# PB_ExtenderPlug.net
KiCad netlist of a schematic drawn in Altium Designer
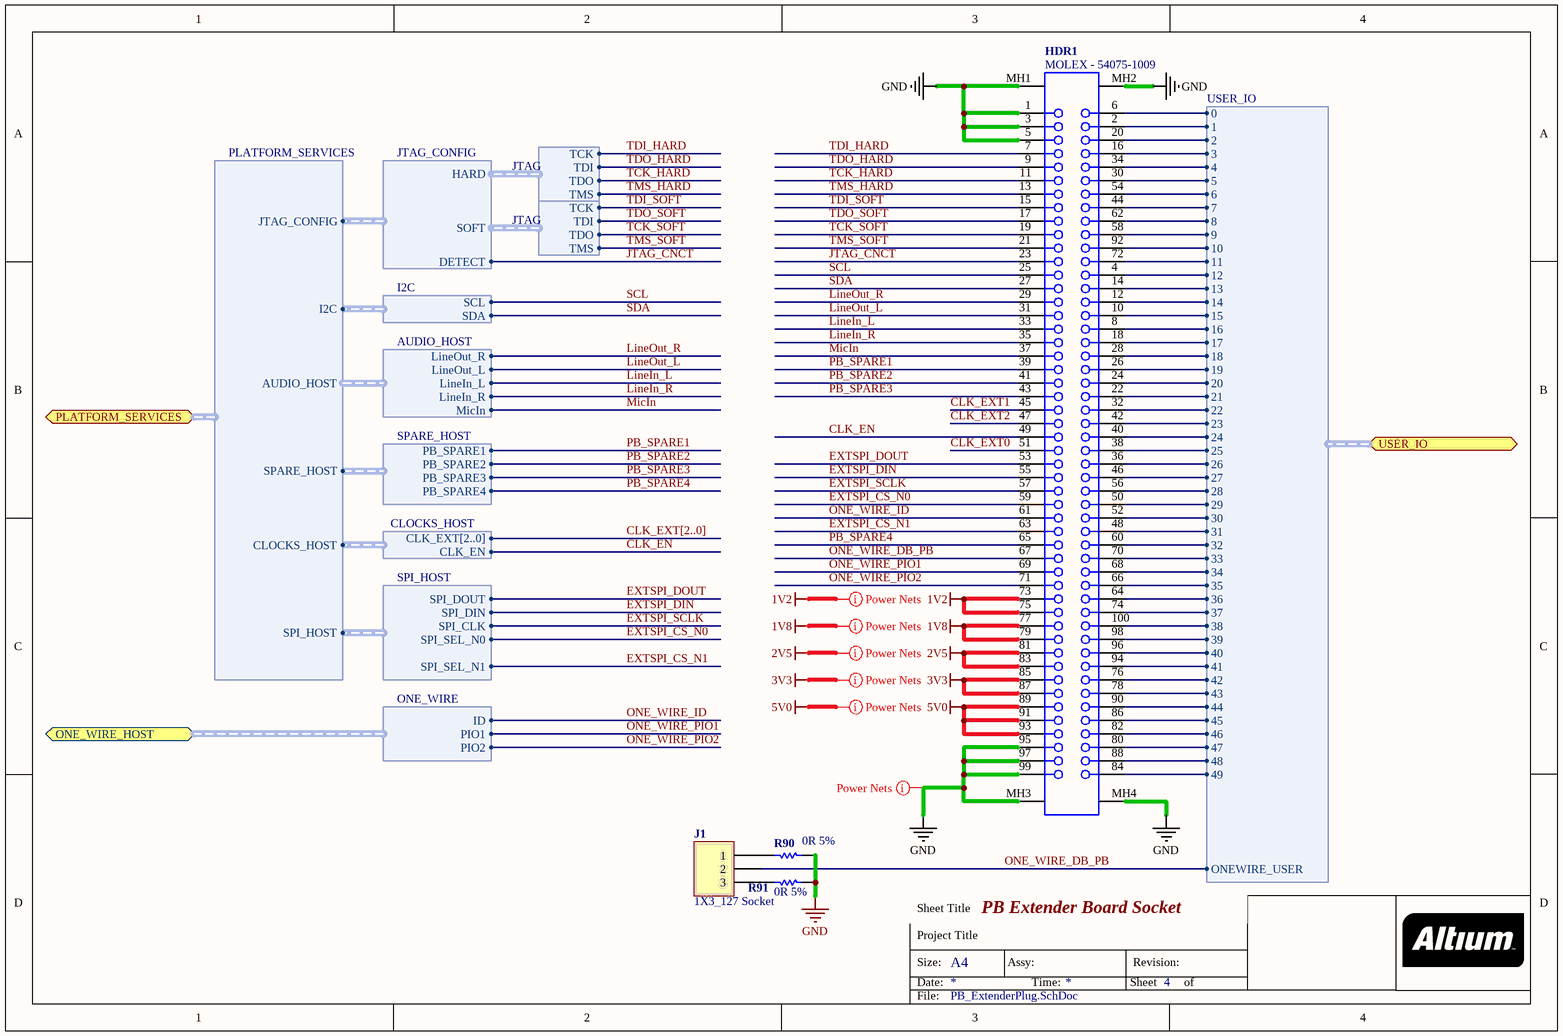
[diagram p0: PB_ExtenderPlug.SchDoc]

(export (version "E")
  (design (tool "Eeschema 10.0.6"))
  (components
    (comp (ref "HDR1")
      (value "MOLEX - 54075-1009")
      (footprint "54075")
      (description "Connector, Molex Docking Station 100 Pin Male 54075")
      (libsource (lib "AltiumDesignLibrary") (part "CON-DOCKSTAT-100-M-STR"))
    )
    (comp (ref "J1")
      (value "1X3_127 Socket")
      (footprint "MHDR1X3_127")
      (description "1X3 Pin Vert 1.27mm Socket")
      (fields (field (name "PUBLISHER") "Altium Limited"))
      (libsource (lib "AltiumDesignLibrary") (part "MHDR1X3_127"))
    )
    (comp (ref "R90")
      (value "0R 5%")
      (footprint "RESC1005-STAR")
      (description "Resistor, 0R 5% 0402 (1005)")
      (fields (field (name "TOLERANCE") "5 %"))
      (libsource (lib "AltiumDesignLibrary") (part "RES"))
    )
    (comp (ref "R91")
      (value "0R 5%")
      (footprint "RESC1005-STAR")
      (description "Resistor, 0R 5% 0402 (1005)")
      (fields (field (name "TOLERANCE") "5 %"))
      (libsource (lib "AltiumDesignLibrary") (part "RES"))
    )
  )
  (nets
    (net (code "10") (name "/0") (class "Default")
      (node (ref "HDR1") (pin "6") (pinfunction "6_6") (pintype "passive"))
    )
    (net (code "11") (name "/1") (class "Default")
      (node (ref "HDR1") (pin "2") (pinfunction "2_2") (pintype "passive"))
    )
    (net (code "12") (name "/2") (class "Default")
      (node (ref "HDR1") (pin "20") (pinfunction "20_20") (pintype "passive"))
    )
    (net (code "13") (name "/3") (class "Default")
      (node (ref "HDR1") (pin "16") (pinfunction "16_16") (pintype "passive"))
    )
    (net (code "14") (name "/4") (class "Default")
      (node (ref "HDR1") (pin "34") (pinfunction "34_34") (pintype "passive"))
    )
    (net (code "15") (name "/5") (class "Default")
      (node (ref "HDR1") (pin "30") (pinfunction "30_30") (pintype "passive"))
    )
    (net (code "16") (name "/6") (class "Default")
      (node (ref "HDR1") (pin "54") (pinfunction "54_54") (pintype "passive"))
    )
    (net (code "17") (name "/7") (class "Default")
      (node (ref "HDR1") (pin "44") (pinfunction "44_44") (pintype "passive"))
    )
    (net (code "18") (name "/8") (class "Default")
      (node (ref "HDR1") (pin "62") (pinfunction "62_62") (pintype "passive"))
    )
    (net (code "19") (name "/9") (class "Default")
      (node (ref "HDR1") (pin "58") (pinfunction "58_58") (pintype "passive"))
    )
    (net (code "20") (name "/10") (class "Default")
      (node (ref "HDR1") (pin "92") (pinfunction "92_92") (pintype "passive"))
    )
    (net (code "21") (name "/11") (class "Default")
      (node (ref "HDR1") (pin "72") (pinfunction "72_72") (pintype "passive"))
    )
    (net (code "22") (name "/12") (class "Default")
      (node (ref "HDR1") (pin "4") (pinfunction "4_4") (pintype "passive"))
    )
    (net (code "23") (name "/13") (class "Default")
      (node (ref "HDR1") (pin "14") (pinfunction "14_14") (pintype "passive"))
    )
    (net (code "24") (name "/14") (class "Default")
      (node (ref "HDR1") (pin "12") (pinfunction "12_12") (pintype "passive"))
    )
    (net (code "25") (name "/15") (class "Default")
      (node (ref "HDR1") (pin "10") (pinfunction "10_10") (pintype "passive"))
    )
    (net (code "26") (name "/16") (class "Default")
      (node (ref "HDR1") (pin "8") (pinfunction "8_8") (pintype "passive"))
    )
    (net (code "27") (name "/17") (class "Default")
      (node (ref "HDR1") (pin "18") (pinfunction "18_18") (pintype "passive"))
    )
    (net (code "28") (name "/18") (class "Default")
      (node (ref "HDR1") (pin "28") (pinfunction "28_28") (pintype "passive"))
    )
    (net (code "29") (name "/19") (class "Default")
      (node (ref "HDR1") (pin "26") (pinfunction "26_26") (pintype "passive"))
    )
    (net (code "30") (name "/20") (class "Default")
      (node (ref "HDR1") (pin "24") (pinfunction "24_24") (pintype "passive"))
    )
    (net (code "31") (name "/21") (class "Default")
      (node (ref "HDR1") (pin "22") (pinfunction "22_22") (pintype "passive"))
    )
    (net (code "32") (name "/22") (class "Default")
      (node (ref "HDR1") (pin "32") (pinfunction "32_32") (pintype "passive"))
    )
    (net (code "33") (name "/23") (class "Default")
      (node (ref "HDR1") (pin "42") (pinfunction "42_42") (pintype "passive"))
    )
    (net (code "34") (name "/24") (class "Default")
      (node (ref "HDR1") (pin "40") (pinfunction "40_40") (pintype "passive"))
    )
    (net (code "35") (name "/25") (class "Default")
      (node (ref "HDR1") (pin "38") (pinfunction "38_38") (pintype "passive"))
    )
    (net (code "36") (name "/26") (class "Default")
      (node (ref "HDR1") (pin "36") (pinfunction "36_36") (pintype "passive"))
    )
    (net (code "37") (name "/27") (class "Default")
      (node (ref "HDR1") (pin "46") (pinfunction "46_46") (pintype "passive"))
    )
    (net (code "38") (name "/28") (class "Default")
      (node (ref "HDR1") (pin "56") (pinfunction "56_56") (pintype "passive"))
    )
    (net (code "39") (name "/29") (class "Default")
      (node (ref "HDR1") (pin "50") (pinfunction "50_50") (pintype "passive"))
    )
    (net (code "40") (name "/30") (class "Default")
      (node (ref "HDR1") (pin "52") (pinfunction "52_52") (pintype "passive"))
    )
    (net (code "41") (name "/31") (class "Default")
      (node (ref "HDR1") (pin "48") (pinfunction "48_48") (pintype "passive"))
    )
    (net (code "42") (name "/32") (class "Default")
      (node (ref "HDR1") (pin "60") (pinfunction "60_60") (pintype "passive"))
    )
    (net (code "43") (name "/33") (class "Default")
      (node (ref "HDR1") (pin "70") (pinfunction "70_70") (pintype "passive"))
    )
    (net (code "44") (name "/34") (class "Default")
      (node (ref "HDR1") (pin "68") (pinfunction "68_68") (pintype "passive"))
    )
    (net (code "45") (name "/35") (class "Default")
      (node (ref "HDR1") (pin "66") (pinfunction "66_66") (pintype "passive"))
    )
    (net (code "46") (name "/36") (class "Default")
      (node (ref "HDR1") (pin "64") (pinfunction "64_64") (pintype "passive"))
    )
    (net (code "47") (name "/37") (class "Default")
      (node (ref "HDR1") (pin "74") (pinfunction "74_74") (pintype "passive"))
    )
    (net (code "48") (name "/38") (class "Default")
      (node (ref "HDR1") (pin "100") (pinfunction "100_100") (pintype "passive"))
    )
    (net (code "49") (name "/39") (class "Default")
      (node (ref "HDR1") (pin "98") (pinfunction "98_98") (pintype "passive"))
    )
    (net (code "50") (name "/40") (class "Default")
      (node (ref "HDR1") (pin "96") (pinfunction "96_96") (pintype "passive"))
    )
    (net (code "51") (name "/41") (class "Default")
      (node (ref "HDR1") (pin "94") (pinfunction "94_94") (pintype "passive"))
    )
    (net (code "52") (name "/42") (class "Default")
      (node (ref "HDR1") (pin "76") (pinfunction "76_76") (pintype "passive"))
    )
    (net (code "53") (name "/43") (class "Default")
      (node (ref "HDR1") (pin "78") (pinfunction "78_78") (pintype "passive"))
    )
    (net (code "54") (name "/44") (class "Default")
      (node (ref "HDR1") (pin "90") (pinfunction "90_90") (pintype "passive"))
    )
    (net (code "55") (name "/45") (class "Default")
      (node (ref "HDR1") (pin "86") (pinfunction "86_86") (pintype "passive"))
    )
    (net (code "56") (name "/46") (class "Default")
      (node (ref "HDR1") (pin "82") (pinfunction "82_82") (pintype "passive"))
    )
    (net (code "57") (name "/47") (class "Default")
      (node (ref "HDR1") (pin "80") (pinfunction "80_80") (pintype "passive"))
    )
    (net (code "58") (name "/48") (class "Default")
      (node (ref "HDR1") (pin "88") (pinfunction "88_88") (pintype "passive"))
    )
    (net (code "59") (name "/49") (class "Default")
      (node (ref "HDR1") (pin "84") (pinfunction "84_84") (pintype "passive"))
    )
    (net (code "60") (name "/CLK_EN") (class "Default")
      (node (ref "HDR1") (pin "49") (pinfunction "49_49") (pintype "passive"))
    )
    (net (code "61") (name "/CLK_EXT0") (class "Default")
      (node (ref "HDR1") (pin "51") (pinfunction "51_51") (pintype "passive"))
    )
    (net (code "62") (name "/CLK_EXT1") (class "Default")
      (node (ref "HDR1") (pin "45") (pinfunction "45_45") (pintype "passive"))
    )
    (net (code "63") (name "/CLK_EXT2") (class "Default")
      (node (ref "HDR1") (pin "47") (pinfunction "47_47") (pintype "passive"))
    )
    (net (code "65") (name "/EXTSPI_CS_N0") (class "Default")
      (node (ref "HDR1") (pin "59") (pinfunction "59_59") (pintype "passive"))
    )
    (net (code "66") (name "/EXTSPI_CS_N1") (class "Default")
      (node (ref "HDR1") (pin "63") (pinfunction "63_63") (pintype "passive"))
    )
    (net (code "67") (name "/EXTSPI_DIN") (class "Default")
      (node (ref "HDR1") (pin "55") (pinfunction "55_55") (pintype "passive"))
    )
    (net (code "68") (name "/EXTSPI_DOUT") (class "Default")
      (node (ref "HDR1") (pin "53") (pinfunction "53_53") (pintype "passive"))
    )
    (net (code "69") (name "/EXTSPI_SCLK") (class "Default")
      (node (ref "HDR1") (pin "57") (pinfunction "57_57") (pintype "passive"))
    )
    (net (code "70") (name "/JTAG_CNCT") (class "Default")
      (node (ref "HDR1") (pin "23") (pinfunction "23_23") (pintype "passive"))
    )
    (net (code "71") (name "/LineIn_L") (class "Default")
      (node (ref "HDR1") (pin "33") (pinfunction "33_33") (pintype "passive"))
    )
    (net (code "72") (name "/LineIn_R") (class "Default")
      (node (ref "HDR1") (pin "35") (pinfunction "35_35") (pintype "passive"))
    )
    (net (code "73") (name "/LineOut_L") (class "Default")
      (node (ref "HDR1") (pin "31") (pinfunction "31_31") (pintype "passive"))
    )
    (net (code "74") (name "/LineOut_R") (class "Default")
      (node (ref "HDR1") (pin "29") (pinfunction "29_29") (pintype "passive"))
    )
    (net (code "75") (name "/MicIn") (class "Default")
      (node (ref "HDR1") (pin "37") (pinfunction "37_37") (pintype "passive"))
    )
    (net (code "76") (name "/ONE_WIRE_DB_PB") (class "Default")
      (node (ref "HDR1") (pin "67") (pinfunction "67_67") (pintype "passive"))
      (node (ref "J1") (pin "2") (pinfunction "2_2") (pintype "passive"))
    )
    (net (code "77") (name "/ONE_WIRE_ID") (class "Default")
      (node (ref "HDR1") (pin "61") (pinfunction "61_61") (pintype "passive"))
    )
    (net (code "78") (name "/ONE_WIRE_PIO1") (class "Default")
      (node (ref "HDR1") (pin "69") (pinfunction "69_69") (pintype "passive"))
    )
    (net (code "79") (name "/ONE_WIRE_PIO2") (class "Default")
      (node (ref "HDR1") (pin "71") (pinfunction "71_71") (pintype "passive"))
    )
    (net (code "80") (name "/PB_SPARE1") (class "Default")
      (node (ref "HDR1") (pin "39") (pinfunction "39_39") (pintype "passive"))
    )
    (net (code "81") (name "/PB_SPARE2") (class "Default")
      (node (ref "HDR1") (pin "41") (pinfunction "41_41") (pintype "passive"))
    )
    (net (code "82") (name "/PB_SPARE3") (class "Default")
      (node (ref "HDR1") (pin "43") (pinfunction "43_43") (pintype "passive"))
    )
    (net (code "83") (name "/PB_SPARE4") (class "Default")
      (node (ref "HDR1") (pin "65") (pinfunction "65_65") (pintype "passive"))
    )
    (net (code "85") (name "/SCL") (class "Default")
      (node (ref "HDR1") (pin "25") (pinfunction "25_25") (pintype "passive"))
    )
    (net (code "86") (name "/SDA") (class "Default")
      (node (ref "HDR1") (pin "27") (pinfunction "27_27") (pintype "passive"))
    )
    (net (code "87") (name "/TCK_HARD") (class "Default")
      (node (ref "HDR1") (pin "11") (pinfunction "11_11") (pintype "passive"))
    )
    (net (code "88") (name "/TCK_SOFT") (class "Default")
      (node (ref "HDR1") (pin "19") (pinfunction "19_19") (pintype "passive"))
    )
    (net (code "89") (name "/TDI_HARD") (class "Default")
      (node (ref "HDR1") (pin "7") (pinfunction "7_7") (pintype "passive"))
    )
    (net (code "90") (name "/TDI_SOFT") (class "Default")
      (node (ref "HDR1") (pin "15") (pinfunction "15_15") (pintype "passive"))
    )
    (net (code "91") (name "/TDO_HARD") (class "Default")
      (node (ref "HDR1") (pin "9") (pinfunction "9_9") (pintype "passive"))
    )
    (net (code "92") (name "/TDO_SOFT") (class "Default")
      (node (ref "HDR1") (pin "17") (pinfunction "17_17") (pintype "passive"))
    )
    (net (code "93") (name "/TMS_HARD") (class "Default")
      (node (ref "HDR1") (pin "13") (pinfunction "13_13") (pintype "passive"))
    )
    (net (code "94") (name "/TMS_SOFT") (class "Default")
      (node (ref "HDR1") (pin "21") (pinfunction "21_21") (pintype "passive"))
    )
    (net (code "103") (name "1V2") (class "Default")
      (node (ref "HDR1") (pin "73") (pinfunction "73_73") (pintype "passive"))
      (node (ref "HDR1") (pin "75") (pinfunction "75_75") (pintype "passive"))
    )
    (net (code "104") (name "1V8") (class "Default")
      (node (ref "HDR1") (pin "77") (pinfunction "77_77") (pintype "passive"))
      (node (ref "HDR1") (pin "79") (pinfunction "79_79") (pintype "passive"))
    )
    (net (code "105") (name "2V5") (class "Default")
      (node (ref "HDR1") (pin "81") (pinfunction "81_81") (pintype "passive"))
      (node (ref "HDR1") (pin "83") (pinfunction "83_83") (pintype "passive"))
    )
    (net (code "106") (name "3V3") (class "Default")
      (node (ref "HDR1") (pin "85") (pinfunction "85_85") (pintype "passive"))
      (node (ref "HDR1") (pin "87") (pinfunction "87_87") (pintype "passive"))
    )
    (net (code "107") (name "5V0") (class "Default")
      (node (ref "HDR1") (pin "89") (pinfunction "89_89") (pintype "passive"))
      (node (ref "HDR1") (pin "91") (pinfunction "91_91") (pintype "passive"))
      (node (ref "HDR1") (pin "93") (pinfunction "93_93") (pintype "passive"))
    )
    (net (code "108") (name "GND") (class "Default")
      (node (ref "HDR1") (pin "1") (pinfunction "1_1") (pintype "passive"))
      (node (ref "HDR1") (pin "3") (pinfunction "3_3") (pintype "passive"))
      (node (ref "HDR1") (pin "5") (pinfunction "5_5") (pintype "passive"))
      (node (ref "HDR1") (pin "95") (pinfunction "95_95") (pintype "passive"))
      (node (ref "HDR1") (pin "97") (pinfunction "97_97") (pintype "passive"))
      (node (ref "HDR1") (pin "99") (pinfunction "99_99") (pintype "passive"))
      (node (ref "HDR1") (pin "MH1") (pinfunction "MH1_MH1") (pintype "passive"))
      (node (ref "HDR1") (pin "MH2") (pinfunction "MH2_MH2") (pintype "passive"))
      (node (ref "HDR1") (pin "MH3") (pinfunction "MH3_MH3") (pintype "passive"))
      (node (ref "HDR1") (pin "MH4") (pinfunction "MH4_MH4") (pintype "passive"))
      (node (ref "R90") (pin "2") (pinfunction "2_2") (pintype "passive"))
      (node (ref "R91") (pin "2") (pinfunction "2_2") (pintype "passive"))
    )
    (net (code "109") (name "Net-(J1-Pad1)") (class "Default")
      (node (ref "J1") (pin "1") (pinfunction "1_1") (pintype "passive"))
      (node (ref "R90") (pin "1") (pinfunction "1_1") (pintype "passive"))
    )
    (net (code "110") (name "Net-(J1-Pad3)") (class "Default")
      (node (ref "J1") (pin "3") (pinfunction "3_3") (pintype "passive"))
      (node (ref "R91") (pin "1") (pinfunction "1_1") (pintype "passive"))
    )
  )
)
